# TR.net
KiCad netlist of a schematic drawn in Altium Designer
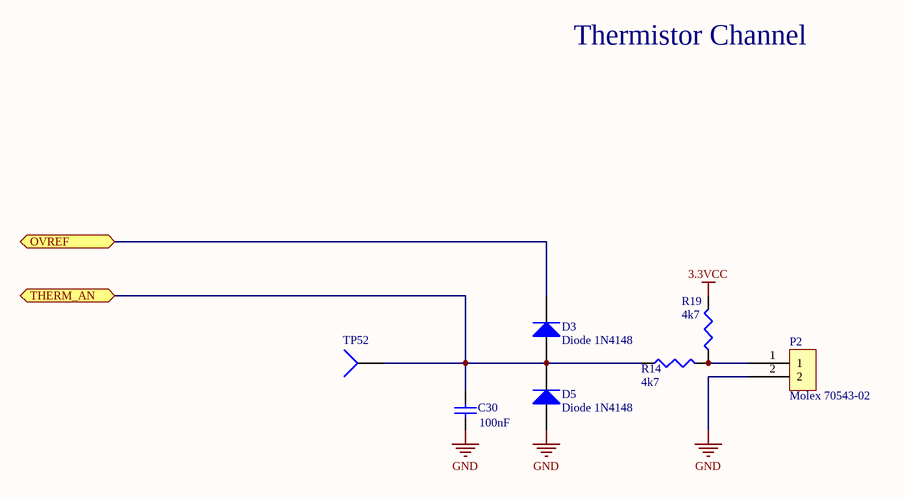
[diagram p0: TR.SchDoc]

(export (version "E")
  (design (tool "Eeschema 10.0.6"))
  (components
    (comp (ref "C30")
      (value "100nF")
      (footprint "1608[0603]")
      (description "Capacitor (Semiconductor SIM Model)")
      (fields (field (name "Comment") "Cap Semi") (field (name "PUBLISHER") "Altium Limited"))
      (libsource (lib "Miscellaneous Devices") (part "Cap Semi"))
    )
    (comp (ref "D3")
      (value "Diode 1N4148")
      (footprint "1N4148WT")
      (description "High Conductance Fast Diode")
      (fields (field (name "PUBLISHER") "Altium Limited"))
      (libsource (lib "Miscellaneous Devices") (part "Diode 1N4148"))
    )
    (comp (ref "D5")
      (value "Diode 1N4148")
      (footprint "1N4148WT")
      (description "High Conductance Fast Diode")
      (fields (field (name "PUBLISHER") "Altium Limited"))
      (libsource (lib "Miscellaneous Devices") (part "Diode 1N4148"))
    )
    (comp (ref "P2")
      (value "Molex 70543-02")
      (footprint "70543-02")
      (libsource (lib "ZMBo Schematic Library") (part "Molex 70543-02"))
    )
    (comp (ref "R14")
      (value "4k7")
      (footprint "J1-0603")
      (description "Resistor")
      (fields (field (name "Comment") "Res3") (field (name "PUBLISHER") "Altium Limited"))
      (libsource (lib "Miscellaneous Devices") (part "Res3"))
    )
    (comp (ref "R19")
      (value "4k7")
      (footprint "J1-0603")
      (description "Resistor")
      (fields (field (name "Comment") "Res3") (field (name "PUBLISHER") "Altium Limited"))
      (libsource (lib "Miscellaneous Devices") (part "Res3"))
    )
    (comp (ref "TP52")
      (value "TP4")
      (footprint "TP-2")
      (description "Socket")
      (fields (field (name "PUBLISHER") "Altium Limited"))
      (libsource (lib "ZMBo Schematic Library") (part "Socket"))
    )
  )
  (nets
    (net (code "1") (name "/OVREF") (class "Default")
      (node (ref "D3") (pin "2") (pinfunction "K_2") (pintype "passive"))
    )
    (net (code "2") (name "/THERM_AN") (class "Default")
      (node (ref "C30") (pin "2") (pinfunction "2_2") (pintype "passive"))
      (node (ref "D3") (pin "1") (pinfunction "A_1") (pintype "passive"))
      (node (ref "D5") (pin "2") (pinfunction "K_2") (pintype "passive"))
      (node (ref "R14") (pin "1") (pinfunction "1_1") (pintype "passive"))
      (node (ref "TP52") (pin "1") (pinfunction "1_1") (pintype "passive"))
    )
    (net (code "3") (name "3.3VCC") (class "Default")
      (node (ref "R19") (pin "2") (pinfunction "2_2") (pintype "passive"))
    )
    (net (code "4") (name "GND") (class "Default")
      (node (ref "C30") (pin "1") (pinfunction "1_1") (pintype "passive"))
      (node (ref "D5") (pin "1") (pinfunction "A_1") (pintype "passive"))
      (node (ref "P2") (pin "2") (pinfunction "2_2") (pintype "passive"))
    )
    (net (code "5") (name "Net-(P2-Pad1)") (class "Default")
      (node (ref "P2") (pin "1") (pinfunction "1_1") (pintype "passive"))
      (node (ref "R14") (pin "2") (pinfunction "2_2") (pintype "passive"))
      (node (ref "R19") (pin "1") (pinfunction "1_1") (pintype "passive"))
    )
  )
)
